# Line_Protection.net
KiCad netlist of a schematic drawn in EAGLE
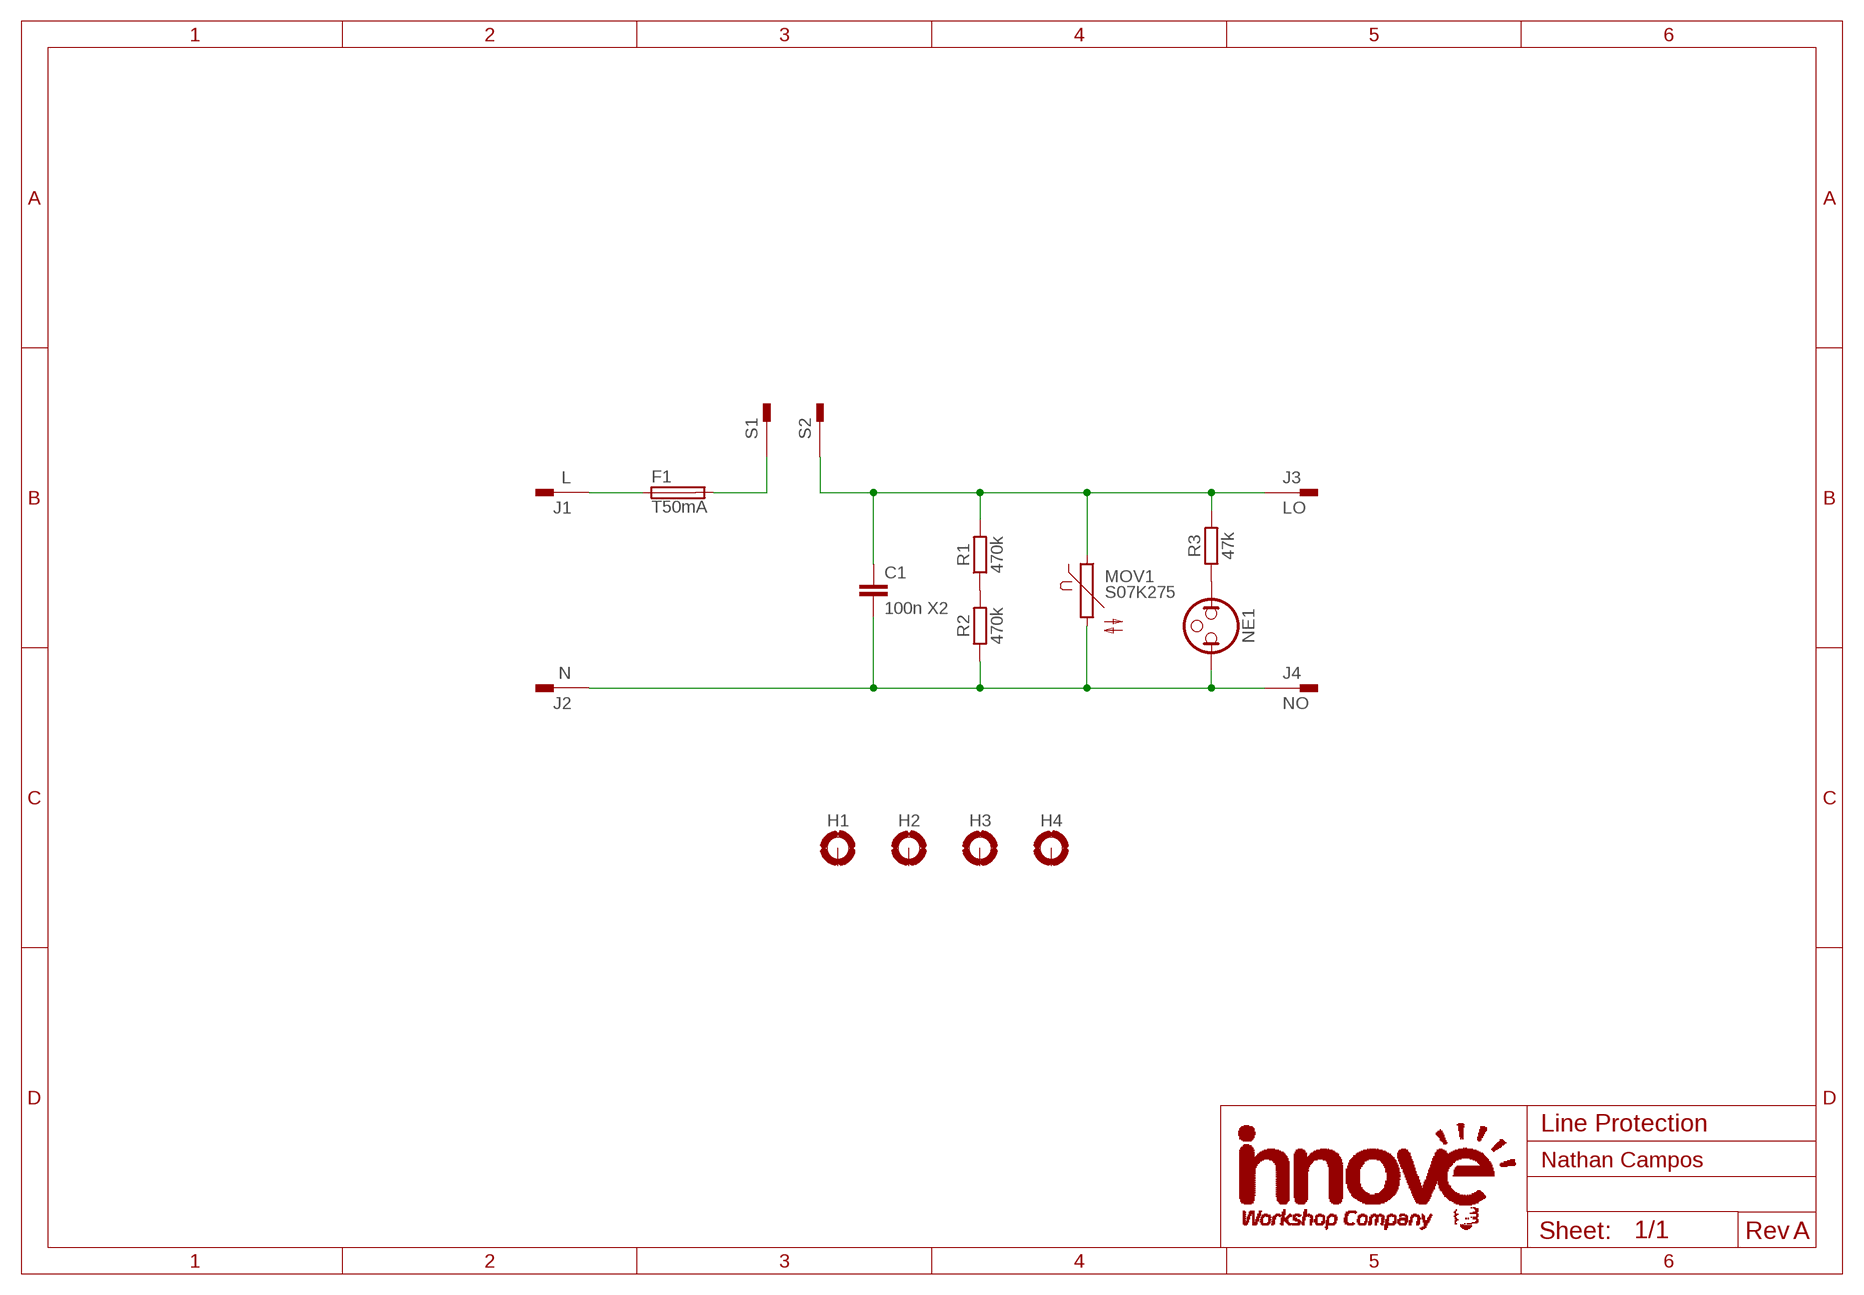
[diagram p0: schematic, sheet 1]

(export (version "E")
  (design (tool "Eeschema 10.0.6"))
  (components
    (comp (ref "C1")
      (value "100n X2")
      (footprint "eagle-import:C150-054X183")
      (libsource (lib "eagle-import") (part "C15-5.4X18.3"))
    )
    (comp (ref "F1")
      (value "T50mA")
      (footprint "eagle-import:CFH14")
      (libsource (lib "eagle-import") (part "CFH14"))
    )
    (comp (ref "H1")
      (value "MOUNT-PAD-ROUND3.0")
      (footprint "eagle-import:3,0-PAD")
      (libsource (lib "eagle-import") (part "MOUNT-PAD-ROUND3.0"))
    )
    (comp (ref "H2")
      (value "MOUNT-PAD-ROUND3.0")
      (footprint "eagle-import:3,0-PAD")
      (libsource (lib "eagle-import") (part "MOUNT-PAD-ROUND3.0"))
    )
    (comp (ref "H3")
      (value "MOUNT-PAD-ROUND3.0")
      (footprint "eagle-import:3,0-PAD")
      (libsource (lib "eagle-import") (part "MOUNT-PAD-ROUND3.0"))
    )
    (comp (ref "H4")
      (value "MOUNT-PAD-ROUND3.0")
      (footprint "eagle-import:3,0-PAD")
      (libsource (lib "eagle-import") (part "MOUNT-PAD-ROUND3.0"))
    )
    (comp (ref "J1")
      (value "L")
      (footprint "eagle-import:F061.100")
      (libsource (lib "eagle-import") (part "FASTON-250D140"))
    )
    (comp (ref "J2")
      (value "N")
      (footprint "eagle-import:F061.100")
      (libsource (lib "eagle-import") (part "FASTON-250D140"))
    )
    (comp (ref "J3")
      (value "LO")
      (footprint "eagle-import:F061.100")
      (libsource (lib "eagle-import") (part "FASTON-250D140"))
    )
    (comp (ref "J4")
      (value "NO")
      (footprint "eagle-import:F061.100")
      (libsource (lib "eagle-import") (part "FASTON-250D140"))
    )
    (comp (ref "MOV1")
      (value "S07K275")
      (footprint "eagle-import:S07K275")
      (libsource (lib "eagle-import") (part "S07K275"))
    )
    (comp (ref "NE1")
      (value "NEON-T2")
      (footprint "eagle-import:NEON-T2")
      (libsource (lib "eagle-import") (part "NEON-T2"))
    )
    (comp (ref "R1")
      (value "470k")
      (footprint "eagle-import:0207_10")
      (libsource (lib "eagle-import") (part "RT0207"))
    )
    (comp (ref "R2")
      (value "470k")
      (footprint "eagle-import:0207_10")
      (libsource (lib "eagle-import") (part "RT0207"))
    )
    (comp (ref "R3")
      (value "47k")
      (footprint "eagle-import:0207_10")
      (libsource (lib "eagle-import") (part "RT0207"))
    )
    (comp (ref "S1")
      (value "FASTON-250D140")
      (footprint "eagle-import:F061.100")
      (libsource (lib "eagle-import") (part "FASTON-250D140"))
    )
    (comp (ref "S2")
      (value "FASTON-250D140")
      (footprint "eagle-import:F061.100")
      (libsource (lib "eagle-import") (part "FASTON-250D140"))
    )
  )
  (nets
    (net (code "1") (name "Net-(C1-Pad1)") (class "Default")
      (node (ref "C1") (pin "1") (pinfunction "1_1") (pintype "passive"))
      (node (ref "J3") (pin "A1") (pinfunction "1_A1") (pintype "passive"))
      (node (ref "J3") (pin "A2") (pinfunction "1_A2") (pintype "passive"))
      (node (ref "MOV1") (pin "1") (pinfunction "1_1") (pintype "passive"))
      (node (ref "R1") (pin "2") (pinfunction "2_2") (pintype "passive"))
      (node (ref "R3") (pin "2") (pinfunction "2_2") (pintype "passive"))
      (node (ref "S2") (pin "A1") (pinfunction "1_A1") (pintype "passive"))
      (node (ref "S2") (pin "A2") (pinfunction "1_A2") (pintype "passive"))
    )
    (net (code "2") (name "Net-(C1-Pad2)") (class "Default")
      (node (ref "C1") (pin "2") (pinfunction "2_2") (pintype "passive"))
      (node (ref "J2") (pin "A1") (pinfunction "1_A1") (pintype "passive"))
      (node (ref "J2") (pin "A2") (pinfunction "1_A2") (pintype "passive"))
      (node (ref "J4") (pin "A1") (pinfunction "1_A1") (pintype "passive"))
      (node (ref "J4") (pin "A2") (pinfunction "1_A2") (pintype "passive"))
      (node (ref "MOV1") (pin "2") (pinfunction "2_2") (pintype "passive"))
      (node (ref "NE1") (pin "2") (pinfunction "2_2") (pintype "passive"))
      (node (ref "R2") (pin "1") (pinfunction "1_1") (pintype "passive"))
    )
    (net (code "3") (name "Net-(F1-Pad1)") (class "Default")
      (node (ref "F1") (pin "1") (pinfunction "1_1") (pintype "passive"))
      (node (ref "J1") (pin "A1") (pinfunction "1_A1") (pintype "passive"))
      (node (ref "J1") (pin "A2") (pinfunction "1_A2") (pintype "passive"))
    )
    (net (code "4") (name "Net-(F1-Pad2)") (class "Default")
      (node (ref "F1") (pin "2") (pinfunction "2_2") (pintype "passive"))
      (node (ref "S1") (pin "A1") (pinfunction "1_A1") (pintype "passive"))
      (node (ref "S1") (pin "A2") (pinfunction "1_A2") (pintype "passive"))
    )
    (net (code "5") (name "Net-(NE1-Pad1)") (class "Default")
      (node (ref "NE1") (pin "1") (pinfunction "1_1") (pintype "passive"))
      (node (ref "R3") (pin "1") (pinfunction "1_1") (pintype "passive"))
    )
    (net (code "6") (name "Net-(R1-Pad1)") (class "Default")
      (node (ref "R1") (pin "1") (pinfunction "1_1") (pintype "passive"))
      (node (ref "R2") (pin "2") (pinfunction "2_2") (pintype "passive"))
    )
    (net (code "7") (name "unconnected-(H1-MOUNT-PadB3,0)") (class "Default")
      (node (ref "H1") (pin "B3,0") (pinfunction "MOUNT_B3,0") (pintype "passive"))
    )
    (net (code "8") (name "unconnected-(H2-MOUNT-PadB3,0)") (class "Default")
      (node (ref "H2") (pin "B3,0") (pinfunction "MOUNT_B3,0") (pintype "passive"))
    )
    (net (code "9") (name "unconnected-(H3-MOUNT-PadB3,0)") (class "Default")
      (node (ref "H3") (pin "B3,0") (pinfunction "MOUNT_B3,0") (pintype "passive"))
    )
    (net (code "10") (name "unconnected-(H4-MOUNT-PadB3,0)") (class "Default")
      (node (ref "H4") (pin "B3,0") (pinfunction "MOUNT_B3,0") (pintype "passive"))
    )
  )
)
